# Power.net
KiCad netlist of a schematic drawn in Altium Designer
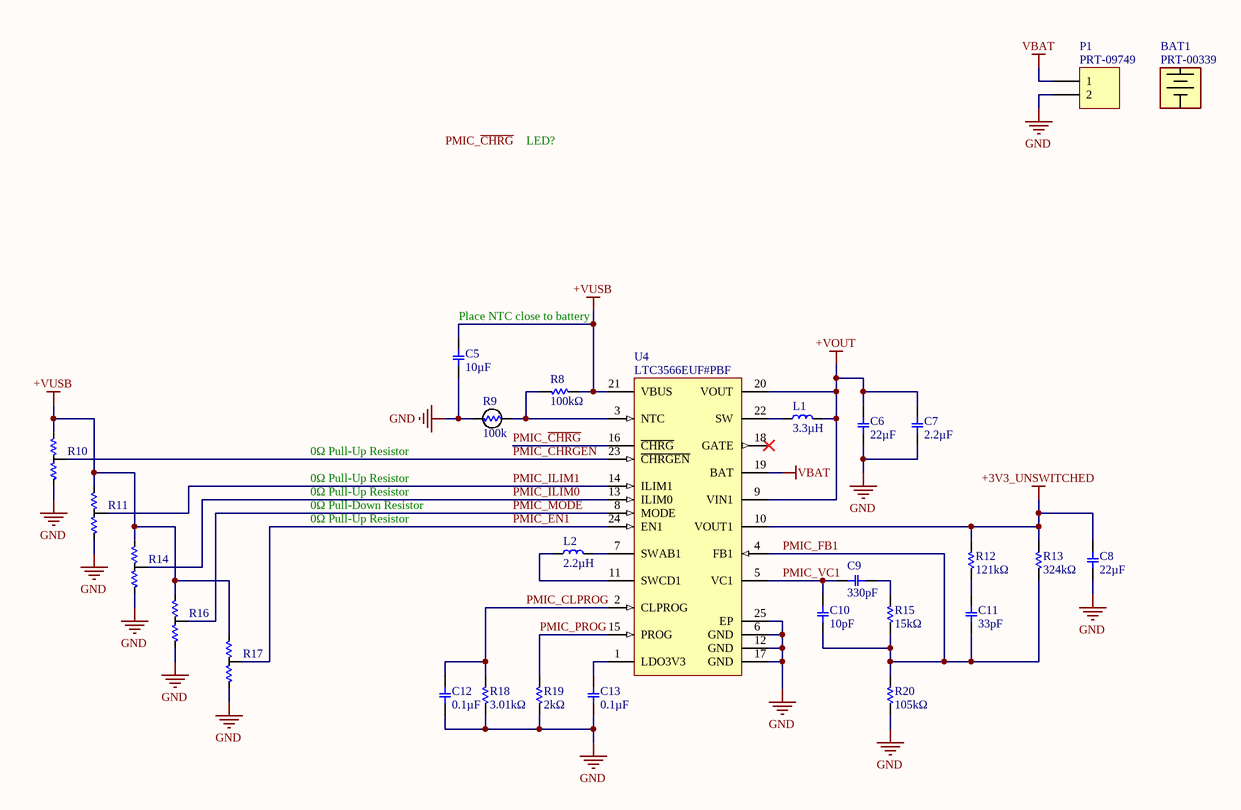
[diagram p0: Power.SchDoc]

(export (version "E")
  (design (tool "Eeschema 10.0.6"))
  (components
    (comp (ref "BAT1")
      (value "PRT-00339")
      (footprint "LiPo Battery - 1000mA")
      (description "Polymer Lithium Ion Battery - 1000mAh")
      (libsource (lib "RFIDSchematicLibrary") (part "PRT-00339"))
    )
    (comp (ref "C5")
      (value "10µF")
      (footprint "C0805(2012)_NP_med")
      (description "SMT Capacitor")
      (fields (field (name "TOLERANCE") "X7R"))
      (libsource (lib "ChipComponents") (part "CPN_SMT"))
    )
    (comp (ref "C6")
      (value "22µF")
      (footprint "C0805(2012)_NP_med")
      (description "SMT Capacitor")
      (fields (field (name "TOLERANCE") "X7R"))
      (libsource (lib "ChipComponents") (part "CPN_SMT"))
    )
    (comp (ref "C7")
      (value "2.2µF")
      (footprint "C0805(2012)_NP_med")
      (description "SMT Capacitor")
      (fields (field (name "TOLERANCE") "X7R"))
      (libsource (lib "ChipComponents") (part "CPN_SMT"))
    )
    (comp (ref "C8")
      (value "22µF")
      (footprint "C0805(2012)_NP_med")
      (description "SMT Capacitor")
      (fields (field (name "TOLERANCE") "X7R"))
      (libsource (lib "ChipComponents") (part "CPN_SMT"))
    )
    (comp (ref "C9")
      (value "330pF")
      (footprint "C0805(2012)_NP_med")
      (description "SMT Capacitor")
      (fields (field (name "TOLERANCE") "X7R"))
      (libsource (lib "ChipComponents") (part "CPN_SMT"))
    )
    (comp (ref "C10")
      (value "10pF")
      (footprint "C0805(2012)_NP_med")
      (description "SMT Capacitor")
      (fields (field (name "TOLERANCE") "X7R"))
      (libsource (lib "ChipComponents") (part "CPN_SMT"))
    )
    (comp (ref "C11")
      (value "33pF")
      (footprint "C0805(2012)_NP_med")
      (description "SMT Capacitor")
      (fields (field (name "TOLERANCE") "X7R"))
      (libsource (lib "ChipComponents") (part "CPN_SMT"))
    )
    (comp (ref "C12")
      (value "0.1µF")
      (footprint "C0805(2012)_NP_med")
      (description "SMT Capacitor")
      (fields (field (name "TOLERANCE") "X7R"))
      (libsource (lib "ChipComponents") (part "CPN_SMT"))
    )
    (comp (ref "C13")
      (value "0.1µF")
      (footprint "C0805(2012)_NP_med")
      (description "SMT Capacitor")
      (fields (field (name "TOLERANCE") "X7R"))
      (libsource (lib "ChipComponents") (part "CPN_SMT"))
    )
    (comp (ref "L1")
      (value "Wurth 744043003")
      (footprint "WURTH WE-TPC 4828")
      (description "FIXED IND 3.3UH 2.15A 35 MOHM")
      (fields
        (field (name "MANUFACTURER") "Wurth Electronics Inc")
        (field (name "MANUFACTURER PART NUMBER") "744043003")
        (field (name "INDUCTANCE") "3.3µH")
      )
      (libsource (lib "RFIDSchematicLibrary") (part "Wurth 744043003"))
    )
    (comp (ref "L2")
      (value "Wurth 7440430022")
      (footprint "WURTH WE-TPC 4828")
      (description "FIXED IND 2.2UH 2.5A 28 MOHM SMD")
      (fields
        (field (name "MANUFACTURER") "Wurth Electronics Inc")
        (field (name "MANUFACTURER PART NUMBER") "7440430022")
        (field (name "INDUCTANCE") "2.2µH")
      )
      (libsource (lib "RFIDSchematicLibrary") (part "Wurth 7440430022"))
    )
    (comp (ref "P1")
      (value "PRT-09749")
      (footprint "SPARKFUN PRT-09749")
      (description "Header, 2-Pin")
      (libsource (lib "Miscellaneous Connectors") (part "Header 2"))
    )
    (comp (ref "R8")
      (value "100kΩ")
      (footprint "R0805(2012)_med")
      (description "SMT resistor")
      (fields (field (name "TOLERANCE") "1%"))
      (libsource (lib "ChipComponents") (part "RES_SMT"))
    )
    (comp (ref "R9")
      (value "Vishay NTCS0805E3104FXT")
      (footprint "R0805(2012)_med")
      (description "THERMISTOR NTC 100K OHM 1% 0805")
      (fields
        (field (name "MANUFACTURER") "Vishay BC Components")
        (field (name "MANUFACTURER PART NUMBER") "NTCS0805E3104FXT")
        (field (name "RESISTANCE IN OHMS @ 25°C") "100k")
      )
      (libsource (lib "RFIDSchematicLibrary") (part "Vishay NTCS0805E3104FXT"))
    )
    (comp (ref "R10")
      (value "0")
      (footprint "R0805(2012)_med_double")
      (description "SMT resistor")
      (fields (field (name "TOLERANCE") "1%"))
      (libsource (lib "RFIDSchematicLibrary") (part "RES_SMT_NONPOP"))
    )
    (comp (ref "R11")
      (value "0")
      (footprint "R0805(2012)_med_double")
      (description "SMT resistor")
      (fields (field (name "TOLERANCE") "1%"))
      (libsource (lib "RFIDSchematicLibrary") (part "RES_SMT_NONPOP"))
    )
    (comp (ref "R12")
      (value "121kΩ")
      (footprint "R0805(2012)_med")
      (description "SMT resistor")
      (fields (field (name "TOLERANCE") "1%"))
      (libsource (lib "ChipComponents") (part "RES_SMT"))
    )
    (comp (ref "R13")
      (value "324kΩ")
      (footprint "R0805(2012)_med")
      (description "SMT resistor")
      (fields (field (name "TOLERANCE") "1%"))
      (libsource (lib "ChipComponents") (part "RES_SMT"))
    )
    (comp (ref "R14")
      (value "0")
      (footprint "R0805(2012)_med_double")
      (description "SMT resistor")
      (fields (field (name "TOLERANCE") "1%"))
      (libsource (lib "RFIDSchematicLibrary") (part "RES_SMT_NONPOP"))
    )
    (comp (ref "R15")
      (value "15kΩ")
      (footprint "R0805(2012)_med")
      (description "SMT resistor")
      (fields (field (name "TOLERANCE") "1%"))
      (libsource (lib "ChipComponents") (part "RES_SMT"))
    )
    (comp (ref "R16")
      (value "0")
      (footprint "R0805(2012)_med_double")
      (description "SMT resistor")
      (fields (field (name "TOLERANCE") "1%"))
      (libsource (lib "RFIDSchematicLibrary") (part "RES_SMT_NONPOP"))
    )
    (comp (ref "R17")
      (value "0")
      (footprint "R0805(2012)_med_double")
      (description "SMT resistor")
      (fields (field (name "TOLERANCE") "1%"))
      (libsource (lib "RFIDSchematicLibrary") (part "RES_SMT_NONPOP"))
    )
    (comp (ref "R18")
      (value "3.01kΩ")
      (footprint "R0805(2012)_med")
      (description "SMT resistor")
      (fields (field (name "TOLERANCE") "1%"))
      (libsource (lib "ChipComponents") (part "RES_SMT"))
    )
    (comp (ref "R19")
      (value "2kΩ")
      (footprint "R0805(2012)_med")
      (description "SMT resistor")
      (fields (field (name "TOLERANCE") "1%"))
      (libsource (lib "ChipComponents") (part "RES_SMT"))
    )
    (comp (ref "R20")
      (value "105kΩ")
      (footprint "R0805(2012)_med")
      (description "SMT resistor")
      (fields (field (name "TOLERANCE") "1%"))
      (libsource (lib "ChipComponents") (part "RES_SMT"))
    )
    (comp (ref "U4")
      (value "LTC3566EUF#PBF")
      (footprint "LT-UF-24_N")
      (fields (field (name "MANUFACTURER") "Linear Technology"))
      (libsource (lib "Linear Technology Power Management PMIC Multifunction") (part "LTC3566EUF#PBF"))
    )
  )
  (nets
    (net (code "1") (name "+3V3_UNSWITCHED") (class "Default")
      (node (ref "C8") (pin "2") (pinfunction "2_2") (pintype "passive"))
      (node (ref "R12") (pin "1") (pinfunction "1_1") (pintype "passive"))
      (node (ref "R13") (pin "1") (pinfunction "1_1") (pintype "passive"))
      (node (ref "U4") (pin "10") (pinfunction "VOUT1_10") (pintype "power_in"))
    )
    (net (code "2") (name "+VOUT") (class "Default")
      (node (ref "C6") (pin "2") (pinfunction "2_2") (pintype "passive"))
      (node (ref "C7") (pin "2") (pinfunction "2_2") (pintype "passive"))
      (node (ref "L1") (pin "2") (pinfunction "2_2") (pintype "passive"))
      (node (ref "U4") (pin "20") (pinfunction "VOUT_20") (pintype "power_in"))
      (node (ref "U4") (pin "9") (pinfunction "VIN1_9") (pintype "power_in"))
    )
    (net (code "3") (name "+VUSB") (class "Default")
      (node (ref "C5") (pin "2") (pinfunction "2_2") (pintype "passive"))
      (node (ref "R10") (pin "1") (pinfunction "1_1") (pintype "passive"))
      (node (ref "R11") (pin "1") (pinfunction "1_1") (pintype "passive"))
      (node (ref "R14") (pin "1") (pinfunction "1_1") (pintype "passive"))
      (node (ref "R16") (pin "1") (pinfunction "1_1") (pintype "passive"))
      (node (ref "R17") (pin "1") (pinfunction "1_1") (pintype "passive"))
      (node (ref "R8") (pin "2") (pinfunction "2_2") (pintype "passive"))
      (node (ref "U4") (pin "21") (pinfunction "VBUS_21") (pintype "power_in"))
    )
    (net (code "4") (name "/PMIC_CLPROG") (class "Default")
      (node (ref "C12") (pin "1") (pinfunction "1_1") (pintype "passive"))
      (node (ref "R18") (pin "1") (pinfunction "1_1") (pintype "passive"))
      (node (ref "U4") (pin "2") (pinfunction "CLPROG_2") (pintype "input"))
    )
    (net (code "5") (name "/PMIC_EN1") (class "Default")
      (node (ref "R17") (pin "2") (pinfunction "2_2") (pintype "passive"))
      (node (ref "U4") (pin "24") (pinfunction "EN1_24") (pintype "input"))
    )
    (net (code "6") (name "/PMIC_FB1") (class "Default")
      (node (ref "C10") (pin "2") (pinfunction "2_2") (pintype "passive"))
      (node (ref "C11") (pin "1") (pinfunction "1_1") (pintype "passive"))
      (node (ref "R13") (pin "2") (pinfunction "2_2") (pintype "passive"))
      (node (ref "R15") (pin "2") (pinfunction "2_2") (pintype "passive"))
      (node (ref "R20") (pin "1") (pinfunction "1_1") (pintype "passive"))
      (node (ref "U4") (pin "4") (pinfunction "FB1_4") (pintype "input"))
    )
    (net (code "7") (name "/PMIC_ILIM0") (class "Default")
      (node (ref "R14") (pin "2") (pinfunction "2_2") (pintype "passive"))
      (node (ref "U4") (pin "13") (pinfunction "ILIM0_13") (pintype "input"))
    )
    (net (code "8") (name "/PMIC_ILIM1") (class "Default")
      (node (ref "R11") (pin "2") (pinfunction "2_2") (pintype "passive"))
      (node (ref "U4") (pin "14") (pinfunction "ILIM1_14") (pintype "input"))
    )
    (net (code "9") (name "/PMIC_MODE") (class "Default")
      (node (ref "R16") (pin "2") (pinfunction "2_2") (pintype "passive"))
      (node (ref "U4") (pin "8") (pinfunction "MODE_8") (pintype "input"))
    )
    (net (code "10") (name "/PMIC_PROG") (class "Default")
      (node (ref "R19") (pin "1") (pinfunction "1_1") (pintype "passive"))
      (node (ref "U4") (pin "15") (pinfunction "PROG_15") (pintype "input"))
    )
    (net (code "11") (name "/PMIC_VC1") (class "Default")
      (node (ref "C10") (pin "1") (pinfunction "1_1") (pintype "passive"))
      (node (ref "C9") (pin "1") (pinfunction "1_1") (pintype "passive"))
      (node (ref "U4") (pin "5") (pinfunction "VC1_5") (pintype "passive"))
    )
    (net (code "12") (name "/PMIC_~{CHRGEN}") (class "Default")
      (node (ref "R10") (pin "2") (pinfunction "2_2") (pintype "passive"))
      (node (ref "U4") (pin "23") (pinfunction "~{CHRGEN}_23") (pintype "input"))
    )
    (net (code "13") (name "/PMIC_~{CHRG}") (class "Default")
      (node (ref "U4") (pin "16") (pinfunction "~{CHRG}_16") (pintype "tri_state"))
    )
    (net (code "14") (name "GND") (class "Default")
      (node (ref "C12") (pin "2") (pinfunction "2_2") (pintype "passive"))
      (node (ref "C13") (pin "2") (pinfunction "2_2") (pintype "passive"))
      (node (ref "C5") (pin "1") (pinfunction "1_1") (pintype "passive"))
      (node (ref "C6") (pin "1") (pinfunction "1_1") (pintype "passive"))
      (node (ref "C7") (pin "1") (pinfunction "1_1") (pintype "passive"))
      (node (ref "C8") (pin "1") (pinfunction "1_1") (pintype "passive"))
      (node (ref "P1") (pin "2") (pinfunction "2_2") (pintype "passive"))
      (node (ref "R10") (pin "3") (pinfunction "3_3") (pintype "passive"))
      (node (ref "R11") (pin "3") (pinfunction "3_3") (pintype "passive"))
      (node (ref "R14") (pin "3") (pinfunction "3_3") (pintype "passive"))
      (node (ref "R16") (pin "3") (pinfunction "3_3") (pintype "passive"))
      (node (ref "R17") (pin "3") (pinfunction "3_3") (pintype "passive"))
      (node (ref "R18") (pin "2") (pinfunction "2_2") (pintype "passive"))
      (node (ref "R19") (pin "2") (pinfunction "2_2") (pintype "passive"))
      (node (ref "R20") (pin "2") (pinfunction "2_2") (pintype "passive"))
      (node (ref "R9") (pin "1") (pinfunction "1_1") (pintype "passive"))
      (node (ref "U4") (pin "12") (pinfunction "GND_12") (pintype "power_in"))
      (node (ref "U4") (pin "17") (pinfunction "GND_17") (pintype "power_in"))
      (node (ref "U4") (pin "25") (pinfunction "EP_25") (pintype "power_in"))
      (node (ref "U4") (pin "6") (pinfunction "GND_6") (pintype "power_in"))
    )
    (net (code "15") (name "Net-(C9-Pad2)") (class "Default")
      (node (ref "C9") (pin "2") (pinfunction "2_2") (pintype "passive"))
      (node (ref "R15") (pin "1") (pinfunction "1_1") (pintype "passive"))
    )
    (net (code "16") (name "Net-(C11-Pad2)") (class "Default")
      (node (ref "C11") (pin "2") (pinfunction "2_2") (pintype "passive"))
      (node (ref "R12") (pin "2") (pinfunction "2_2") (pintype "passive"))
    )
    (net (code "17") (name "Net-(U4-LDO3V3)") (class "Default")
      (node (ref "C13") (pin "1") (pinfunction "1_1") (pintype "passive"))
      (node (ref "U4") (pin "1") (pinfunction "LDO3V3_1") (pintype "power_in"))
    )
    (net (code "18") (name "Net-(U4-NTC)") (class "Default")
      (node (ref "R8") (pin "1") (pinfunction "1_1") (pintype "passive"))
      (node (ref "R9") (pin "2") (pinfunction "2_2") (pintype "passive"))
      (node (ref "U4") (pin "3") (pinfunction "NTC_3") (pintype "input"))
    )
    (net (code "19") (name "Net-(U4-SW)") (class "Default")
      (node (ref "L1") (pin "1") (pinfunction "1_1") (pintype "passive"))
      (node (ref "U4") (pin "22") (pinfunction "SW_22") (pintype "power_in"))
    )
    (net (code "20") (name "Net-(U4-SWAB1)") (class "Default")
      (node (ref "L2") (pin "2") (pinfunction "2_2") (pintype "passive"))
      (node (ref "U4") (pin "7") (pinfunction "SWAB1_7") (pintype "passive"))
    )
    (net (code "21") (name "Net-(U4-SWCD1)") (class "Default")
      (node (ref "L2") (pin "1") (pinfunction "1_1") (pintype "passive"))
      (node (ref "U4") (pin "11") (pinfunction "SWCD1_11") (pintype "passive"))
    )
    (net (code "22") (name "VBAT") (class "Default")
      (node (ref "P1") (pin "1") (pinfunction "1_1") (pintype "passive"))
      (node (ref "U4") (pin "19") (pinfunction "BAT_19") (pintype "power_in"))
    )
    (net (code "23") (name "unconnected-(U4-GATE-Pad18)") (class "Default")
      (node (ref "U4") (pin "18") (pinfunction "GATE_18") (pintype "output+no_connect"))
    )
  )
)
